# Bypass_FPGA_1V2.net
KiCad netlist of a schematic drawn in Altium Designer
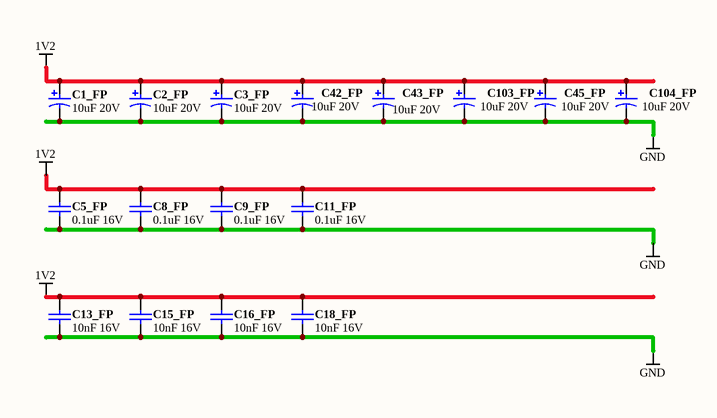
[diagram p0: Bypass_FPGA_1V2.SchDoc]

(export (version "E")
  (design (tool "Eeschema 10.0.6"))
  (components
    (comp (ref "C1_FP")
      (value "10uF 20V")
      (footprint "CAPC3528-STAR")
      (description "Capacitor, Tantalum, 10uF 10% 20V MCCT-B (3528)")
      (fields (field (name "TOLERANCE") "10 %"))
      (libsource (lib "altium-import") (part "root_0_CAP-P_"))
    )
    (comp (ref "C2_FP")
      (value "10uF 20V")
      (footprint "CAPC3528-STAR")
      (description "Capacitor, Tantalum, 10uF 10% 20V MCCT-B (3528)")
      (fields (field (name "TOLERANCE") "10 %"))
      (libsource (lib "altium-import") (part "root_0_CAP-P_"))
    )
    (comp (ref "C3_FP")
      (value "10uF 20V")
      (footprint "CAPC3528-STAR")
      (description "Capacitor, Tantalum, 10uF 10% 20V MCCT-B (3528)")
      (fields (field (name "TOLERANCE") "10 %"))
      (libsource (lib "altium-import") (part "root_0_CAP-P_"))
    )
    (comp (ref "C5_FP")
      (value "0.1uF 16V")
      (footprint "CAPC1005-STAR")
      (description "Capacitor, Ceramic, 0.1uF 10% 16V 0402 (1005) X7R")
      (fields (field (name "TOLERANCE") "10 %"))
      (libsource (lib "altium-import") (part "root_0_mirrored_CAP-NP_"))
    )
    (comp (ref "C8_FP")
      (value "0.1uF 16V")
      (footprint "CAPC1005-STAR")
      (description "Capacitor, Ceramic, 0.1uF 10% 16V 0402 (1005) X7R")
      (fields (field (name "TOLERANCE") "10 %"))
      (libsource (lib "altium-import") (part "root_0_mirrored_CAP-NP_"))
    )
    (comp (ref "C9_FP")
      (value "0.1uF 16V")
      (footprint "CAPC1005-STAR")
      (description "Capacitor, Ceramic, 0.1uF 10% 16V 0402 (1005) X7R")
      (fields (field (name "TOLERANCE") "10 %"))
      (libsource (lib "altium-import") (part "root_0_mirrored_CAP-NP_"))
    )
    (comp (ref "C11_FP")
      (value "0.1uF 16V")
      (footprint "CAPC1005-STAR")
      (description "Capacitor, Ceramic, 0.1uF 10% 16V 0402 (1005) X7R")
      (fields (field (name "TOLERANCE") "10 %"))
      (libsource (lib "altium-import") (part "root_0_mirrored_CAP-NP_"))
    )
    (comp (ref "C13_FP")
      (value "10nF 16V")
      (footprint "CAPC1005-STAR")
      (description "Capacitor, Ceramic, 10nF 10% 16V 0402 (1005) X7R")
      (fields (field (name "TOLERANCE") "10 %"))
      (libsource (lib "altium-import") (part "root_0_CAP-NP_"))
    )
    (comp (ref "C15_FP")
      (value "10nF 16V")
      (footprint "CAPC1005-STAR")
      (description "Capacitor, Ceramic, 10nF 10% 16V 0402 (1005) X7R")
      (fields (field (name "TOLERANCE") "10 %"))
      (libsource (lib "altium-import") (part "root_0_CAP-NP_"))
    )
    (comp (ref "C16_FP")
      (value "10nF 16V")
      (footprint "CAPC1005-STAR")
      (description "Capacitor, Ceramic, 10nF 10% 16V 0402 (1005) X7R")
      (fields (field (name "TOLERANCE") "10 %"))
      (libsource (lib "altium-import") (part "root_0_CAP-NP_"))
    )
    (comp (ref "C18_FP")
      (value "10nF 16V")
      (footprint "CAPC1005-STAR")
      (description "Capacitor, Ceramic, 10nF 10% 16V 0402 (1005) X7R")
      (fields (field (name "TOLERANCE") "10 %"))
      (libsource (lib "altium-import") (part "root_0_CAP-NP_"))
    )
    (comp (ref "C42_FP")
      (value "10uF 20V")
      (footprint "CAPC3528-STAR")
      (description "Capacitor, Tantalum, 10uF 10% 20V MCCT-B (3528)")
      (fields (field (name "TOLERANCE") "10 %"))
      (libsource (lib "altium-import") (part "root_0_CAP-P_"))
    )
    (comp (ref "C43_FP")
      (value "10uF 20V")
      (footprint "CAPC3528-STAR")
      (description "Capacitor, Tantalum, 10uF 10% 20V MCCT-B (3528)")
      (fields (field (name "TOLERANCE") "10 %"))
      (libsource (lib "altium-import") (part "root_0_CAP-P_"))
    )
    (comp (ref "C45_FP")
      (value "10uF 20V")
      (footprint "CAPC3528-STAR")
      (description "Capacitor, Tantalum, 10uF 10% 20V MCCT-B (3528)")
      (fields (field (name "TOLERANCE") "10 %"))
      (libsource (lib "altium-import") (part "root_0_CAP-P_"))
    )
    (comp (ref "C103_FP")
      (value "10uF 20V")
      (footprint "CAPC3528-STAR")
      (description "Capacitor, Tantalum, 10uF 10% 20V MCCT-B (3528)")
      (fields (field (name "TOLERANCE") "10 %"))
      (libsource (lib "altium-import") (part "root_0_CAP-P_"))
    )
    (comp (ref "C104_FP")
      (value "10uF 20V")
      (footprint "CAPC3528-STAR")
      (description "Capacitor, Tantalum, 10uF 10% 20V MCCT-B (3528)")
      (fields (field (name "TOLERANCE") "10 %"))
      (libsource (lib "altium-import") (part "root_0_CAP-P_"))
    )
  )
  (nets
    (net (code "1") (name "1V2") (class "Default")
      (node (ref "C103_FP") (pin "1") (pinfunction "1_1") (pintype "passive"))
      (node (ref "C104_FP") (pin "1") (pinfunction "1_1") (pintype "passive"))
      (node (ref "C11_FP") (pin "1") (pinfunction "1_1") (pintype "passive"))
      (node (ref "C13_FP") (pin "1") (pinfunction "1_1") (pintype "passive"))
      (node (ref "C15_FP") (pin "1") (pinfunction "1_1") (pintype "passive"))
      (node (ref "C16_FP") (pin "1") (pinfunction "1_1") (pintype "passive"))
      (node (ref "C18_FP") (pin "1") (pinfunction "1_1") (pintype "passive"))
      (node (ref "C1_FP") (pin "1") (pinfunction "1_1") (pintype "passive"))
      (node (ref "C2_FP") (pin "1") (pinfunction "1_1") (pintype "passive"))
      (node (ref "C3_FP") (pin "1") (pinfunction "1_1") (pintype "passive"))
      (node (ref "C42_FP") (pin "1") (pinfunction "1_1") (pintype "passive"))
      (node (ref "C43_FP") (pin "1") (pinfunction "1_1") (pintype "passive"))
      (node (ref "C45_FP") (pin "1") (pinfunction "1_1") (pintype "passive"))
      (node (ref "C5_FP") (pin "1") (pinfunction "1_1") (pintype "passive"))
      (node (ref "C8_FP") (pin "1") (pinfunction "1_1") (pintype "passive"))
      (node (ref "C9_FP") (pin "1") (pinfunction "1_1") (pintype "passive"))
    )
    (net (code "2") (name "GND") (class "Default")
      (node (ref "C103_FP") (pin "2") (pinfunction "2_2") (pintype "passive"))
      (node (ref "C104_FP") (pin "2") (pinfunction "2_2") (pintype "passive"))
      (node (ref "C11_FP") (pin "2") (pinfunction "2_2") (pintype "passive"))
      (node (ref "C13_FP") (pin "2") (pinfunction "2_2") (pintype "passive"))
      (node (ref "C15_FP") (pin "2") (pinfunction "2_2") (pintype "passive"))
      (node (ref "C16_FP") (pin "2") (pinfunction "2_2") (pintype "passive"))
      (node (ref "C18_FP") (pin "2") (pinfunction "2_2") (pintype "passive"))
      (node (ref "C1_FP") (pin "2") (pinfunction "2_2") (pintype "passive"))
      (node (ref "C2_FP") (pin "2") (pinfunction "2_2") (pintype "passive"))
      (node (ref "C3_FP") (pin "2") (pinfunction "2_2") (pintype "passive"))
      (node (ref "C42_FP") (pin "2") (pinfunction "2_2") (pintype "passive"))
      (node (ref "C43_FP") (pin "2") (pinfunction "2_2") (pintype "passive"))
      (node (ref "C45_FP") (pin "2") (pinfunction "2_2") (pintype "passive"))
      (node (ref "C5_FP") (pin "2") (pinfunction "2_2") (pintype "passive"))
      (node (ref "C8_FP") (pin "2") (pinfunction "2_2") (pintype "passive"))
      (node (ref "C9_FP") (pin "2") (pinfunction "2_2") (pintype "passive"))
    )
  )
)
